# Sensor_Box_CAN_Switch.net
KiCad netlist of a schematic drawn in Altium Designer
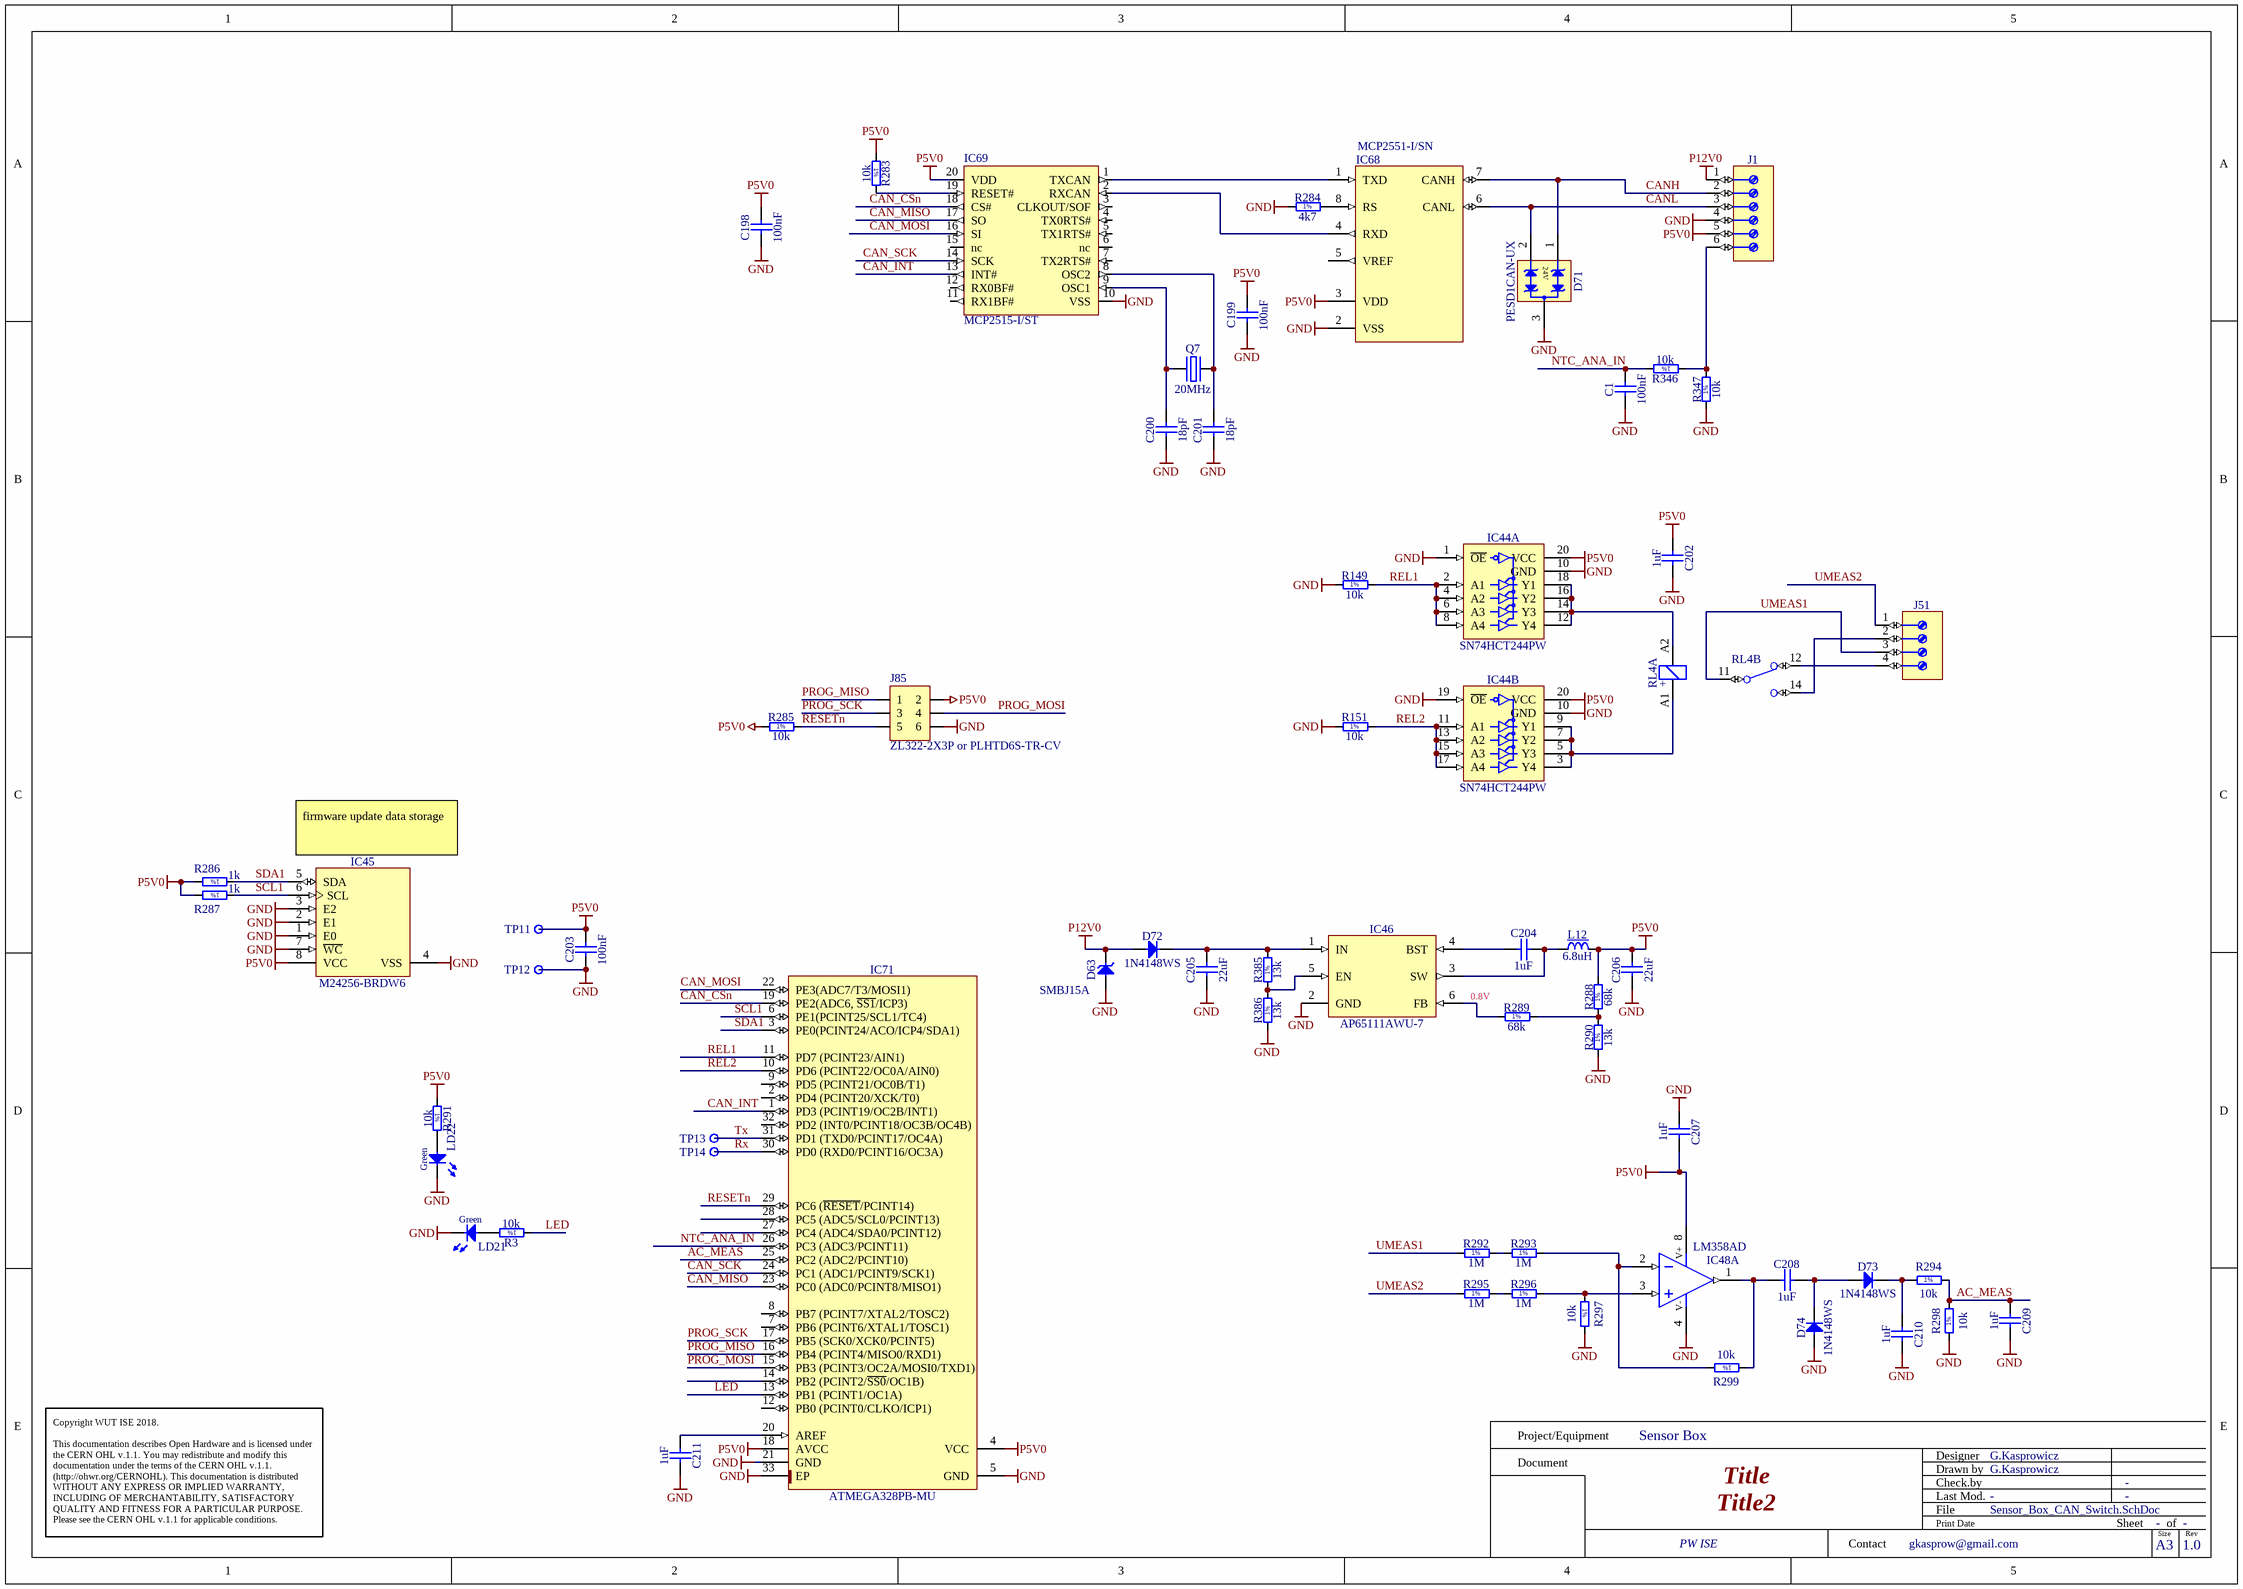
[diagram p0: Sensor_Box_CAN_Switch.SchDoc]

(export (version "E")
  (design (tool "Eeschema 10.0.6"))
  (components
    (comp (ref "C1")
      (value "100nF")
      (footprint "CAPC1005X55N")
      (description "Non-polarised capacitor")
      (fields
        (field (name "PART NUMBER") "CC0402_100NF_16V_10%_X5R")
        (field (name "VOLTAGE") "16V")
        (field (name "AUTHOR") "CERN DEM JLC")
      )
      (libsource (lib "Capacitors") (part "Capacitor - non polarized"))
    )
    (comp (ref "C198")
      (value "100nF")
      (footprint "CAPC1005X55N")
      (description "Non-polarised capacitor")
      (fields
        (field (name "PART NUMBER") "CC0402_100NF_16V_10%_X5R")
        (field (name "VOLTAGE") "16V")
        (field (name "AUTHOR") "CERN DEM JLC")
      )
      (libsource (lib "Capacitors") (part "Capacitor - non polarized"))
    )
    (comp (ref "C199")
      (value "100nF")
      (footprint "CAPC1005X55N")
      (description "Non-polarised capacitor")
      (fields
        (field (name "PART NUMBER") "CC0402_100NF_16V_10%_X5R")
        (field (name "VOLTAGE") "16V")
        (field (name "AUTHOR") "CERN DEM JLC")
      )
      (libsource (lib "Capacitors") (part "Capacitor - non polarized"))
    )
    (comp (ref "C200")
      (value "18pF")
      (footprint "CAPC1005X55N")
      (description "Non-polarised capacitor")
      (fields
        (field (name "PART NUMBER") "CC0402_18PF_50V_5%_C0G")
        (field (name "VOLTAGE") "50V")
        (field (name "AUTHOR") "CERN DEM JLC")
      )
      (libsource (lib "Capacitors") (part "Capacitor - non polarized"))
    )
    (comp (ref "C201")
      (value "18pF")
      (footprint "CAPC1005X55N")
      (description "Non-polarised capacitor")
      (fields
        (field (name "PART NUMBER") "CC0402_18PF_50V_5%_C0G")
        (field (name "VOLTAGE") "50V")
        (field (name "AUTHOR") "CERN DEM JLC")
      )
      (libsource (lib "Capacitors") (part "Capacitor - non polarized"))
    )
    (comp (ref "C202")
      (value "1uF")
      (footprint "CAPC1005X55N")
      (description "Non-polarised capacitor")
      (fields
        (field (name "PART NUMBER") "CC0402_1UF_16V_10%_X5R")
        (field (name "VOLTAGE") "16V")
        (field (name "AUTHOR") "CERN DEM JLC")
      )
      (libsource (lib "Capacitors") (part "Capacitor - non polarized"))
    )
    (comp (ref "C203")
      (value "100nF")
      (footprint "CAPC1005X55N")
      (description "Non-polarised capacitor")
      (fields
        (field (name "PART NUMBER") "CC0402_100NF_16V_10%_X5R")
        (field (name "VOLTAGE") "16V")
        (field (name "AUTHOR") "CERN DEM JLC")
      )
      (libsource (lib "Capacitors") (part "Capacitor - non polarized"))
    )
    (comp (ref "C204")
      (value "1uF")
      (footprint "CAPC1005X55N")
      (description "Non-polarised capacitor")
      (fields
        (field (name "PART NUMBER") "CC0402_1UF_16V_10%_X5R")
        (field (name "VOLTAGE") "16V")
        (field (name "AUTHOR") "CERN DEM JLC")
      )
      (libsource (lib "Capacitors") (part "Capacitor - non polarized"))
    )
    (comp (ref "C205")
      (value "22uF")
      (footprint "CAPC1709X100N")
      (description "Non-polarised capacitor")
      (fields
        (field (name "PART NUMBER") "CC0603_22UF_6.3V_20%_X5R")
        (field (name "VOLTAGE") "6.3V")
        (field (name "AUTHOR") "CERN DEM JLC")
      )
      (libsource (lib "Capacitors") (part "Capacitor - non polarized"))
    )
    (comp (ref "C206")
      (value "22uF")
      (footprint "CAPC1709X100N")
      (description "Non-polarised capacitor")
      (fields
        (field (name "PART NUMBER") "CC0603_22UF_6.3V_20%_X5R")
        (field (name "VOLTAGE") "6.3V")
        (field (name "AUTHOR") "CERN DEM JLC")
      )
      (libsource (lib "Capacitors") (part "Capacitor - non polarized"))
    )
    (comp (ref "C207")
      (value "1uF")
      (footprint "CAPC1005X55N")
      (description "Non-polarised capacitor")
      (fields
        (field (name "PART NUMBER") "CC0402_1UF_16V_10%_X5R")
        (field (name "VOLTAGE") "16V")
        (field (name "AUTHOR") "CERN DEM JLC")
      )
      (libsource (lib "Capacitors") (part "Capacitor - non polarized"))
    )
    (comp (ref "C208")
      (value "1uF")
      (footprint "CAPC1005X55N")
      (description "Non-polarised capacitor")
      (fields
        (field (name "PART NUMBER") "CC0402_1UF_16V_10%_X5R")
        (field (name "VOLTAGE") "16V")
        (field (name "AUTHOR") "CERN DEM JLC")
      )
      (libsource (lib "Capacitors") (part "Capacitor - non polarized"))
    )
    (comp (ref "C209")
      (value "1uF")
      (footprint "CAPC1005X55N")
      (description "Non-polarised capacitor")
      (fields
        (field (name "PART NUMBER") "CC0402_1UF_16V_10%_X5R")
        (field (name "VOLTAGE") "16V")
        (field (name "AUTHOR") "CERN DEM JLC")
      )
      (libsource (lib "Capacitors") (part "Capacitor - non polarized"))
    )
    (comp (ref "C210")
      (value "1uF")
      (footprint "CAPC1005X55N")
      (description "Non-polarised capacitor")
      (fields
        (field (name "PART NUMBER") "CC0402_1UF_16V_10%_X5R")
        (field (name "VOLTAGE") "16V")
        (field (name "AUTHOR") "CERN DEM JLC")
      )
      (libsource (lib "Capacitors") (part "Capacitor - non polarized"))
    )
    (comp (ref "C211")
      (value "1uF")
      (footprint "CAPC1005X55N")
      (description "Non-polarised capacitor")
      (fields
        (field (name "PART NUMBER") "CC0402_1UF_16V_10%_X5R")
        (field (name "VOLTAGE") "16V")
        (field (name "AUTHOR") "CERN DEM JLC")
      )
      (libsource (lib "Capacitors") (part "Capacitor - non polarized"))
    )
    (comp (ref "D63")
      (value "SMBJ15A")
      (footprint "DIOM5336X265N")
      (description "Zener Diode")
      (fields
        (field (name "VOLTAGE") "15V")
        (field (name "POWER") "600W")
        (field (name "AUTHOR") "CERN DEM JLC")
      )
      (libsource (lib "ICs And Semiconductors") (part "Diode Zener"))
    )
    (comp (ref "D71")
      (value "PESD1CAN-UX")
      (footprint "SOT95P237X112-3N")
      (description "TVS Diode for CAN")
      (fields
        (field (name "VOLTAGE") "24V")
        (field (name "POWER") "400W")
        (field (name "AUTHOR") "CERN DEM JLC")
      )
      (libsource (lib "LIBRARY_SCH") (part "D_TVS_PESD1CAN"))
    )
    (comp (ref "D72")
      (value "1N4148WS")
      (footprint "SODFL2512X100N")
      (description "Diode")
      (fields
        (field (name "VOLTAGE") "75V")
        (field (name "POWER") "150mA")
        (field (name "AUTHOR") "CERN DEM JLC")
      )
      (libsource (lib "ICs And Semiconductors") (part "Diode"))
    )
    (comp (ref "D73")
      (value "1N4148WS")
      (footprint "SODFL2512X100N")
      (description "Diode")
      (fields
        (field (name "VOLTAGE") "75V")
        (field (name "POWER") "150mA")
        (field (name "AUTHOR") "CERN DEM JLC")
      )
      (libsource (lib "ICs And Semiconductors") (part "Diode"))
    )
    (comp (ref "D74")
      (value "1N4148WS")
      (footprint "SODFL2512X100N")
      (description "Diode")
      (fields
        (field (name "VOLTAGE") "75V")
        (field (name "POWER") "150mA")
        (field (name "AUTHOR") "CERN DEM JLC")
      )
      (libsource (lib "ICs And Semiconductors") (part "Diode"))
    )
    (comp (ref "IC44")
      (value "SN74HCT244PW")
      (footprint "SOP65P640X120-20N")
      (description "Octal Buffer/Driver with 3-State Ouputs")
      (fields (field (name "MANUFACTURER") "TEXAS INSTRUMENTS") (field (name "AUTHOR") "CERN DEM JLC"))
      (libsource (lib "ICs And Semiconductors") (part "74244_a"))
    )
    (comp (ref "IC45")
      (value "M24256-BRDW6")
      (footprint "SOP65P640X120-8N")
      (description "256-Kbit Serial I²C Bus EEPROM")
      (fields
        (field (name "PART NUMBER") "M24256-BRDW6P")
        (field (name "MANUFACTURER") "ST MICROELECTRONICS")
        (field (name "AUTHOR") "CERN DEM MR")
      )
      (libsource (lib "LIBRARY_SCH") (part "MEM_M24256-BRDW6P"))
    )
    (comp (ref "IC46")
      (value "AP65111AWU-7")
      (footprint "SOT95P280X100-6N")
      (description "Light Load Improved 1.5A Synch DC/DC Buck Converter")
      (fields (field (name "MANUFACTURER") "DIODES INCORPORATED") (field (name "AUTHOR") "CERN DEM JLC"))
      (libsource (lib "ICs And Semiconductors") (part "AP65111A"))
    )
    (comp (ref "IC48")
      (value "LM358AD")
      (footprint "SOIC127P600X175-8N")
      (description "Dual Operational Amplifier")
      (fields (field (name "MANUFACTURER") "TEXAS INSTRUMENTS") (field (name "AUTHOR") "CERN DEM JLC"))
      (libsource (lib "ICs And Semiconductors") (part "Operational Amplifier x2 Type1"))
    )
    (comp (ref "IC68")
      (value "MCP2551-I/SN")
      (footprint "SOIC127P600X175-8N")
      (description "High-Speed CAN Transceiver, 8-Pin SOIC, Industrial Temperature")
      (fields (field (name "MANUFACTURER") "MICROCHIP TECHNOLOGY") (field (name "AUTHOR") "GK"))
      (libsource (lib "LIBRARY_SCH") (part "IFC_MCP2551"))
    )
    (comp (ref "IC69")
      (value "MCP2515-I/ST")
      (footprint "SOP65P640X110-20N")
      (description "CAN Controller With SPI nterface")
      (fields
        (field (name "MANUFACTURER") "Microchip")
        (field (name "MANUFACTURER PART NUMBER") "MCP2515T-I/ST")
      )
      (libsource (lib "LIBRARY_SCH") (part "IFC_MCP2515_TSSOP"))
    )
    (comp (ref "IC71")
      (value "ATMEGA328PB-MU")
      (footprint "QFN50P500X500X100-33N-S325")
      (description "8-bit AVR 20MHz Microcontroller With 32K Bytes In-System  Programmable  Flash")
      (fields (field (name "MANUFACTURER") "ATMEL") (field (name "AUTHOR") "GK"))
      (libsource (lib "LIBRARY_SCH") (part "UPC_ATMEGA328PB-MU"))
    )
    (comp (ref "J1")
      (value "~")
      (footprint "PHOENIX_1725698")
      (description "Terminal Block, 6 Positions, Screw Connection")
      (fields
        (field (name "PART NUMBER") "PHOENIX_1725698")
        (field (name "MANUFACTURER") "PHOENIX CONTACT")
        (field (name "AUTHOR") "CERN DEM JMW")
      )
      (libsource (lib "Connectors") (part "Terminal Block_6 Positions_Screw Connection"))
    )
    (comp (ref "J51")
      (value "~")
      (footprint "TYCO_282836-4")
      (description "Terminal Block, 4 Positions, Screw Connection")
      (fields
        (field (name "PART NUMBER") "TYCO_282836-4")
        (field (name "MANUFACTURER") "TYCO ELECTRONICS")
        (field (name "AUTHOR") "CERN DEM JLC")
      )
      (libsource (lib "Connectors") (part "Terminal Block_4 Positions_Screw Connection"))
    )
    (comp (ref "J85")
      (value "ZL322-2X3P or PLHTD6S-TR-CV")
      (footprint "ZL322-2X3P")
      (description "1.27 mm dual row goldpin (Maritex)")
      (libsource (lib "LIBRARY_SCH") (part "CON_2x3 1.27 SMT Male"))
    )
    (comp (ref "L12")
      (value "6.8uH")
      (footprint "IND_WALSIN_WLPN3030")
      (description "6,8uH; 900mA; 0,211Ω; 3x3x1,5mm")
      (fields
        (field (name "PART NUMBER") "IND_6.8UH_20%_WALSIN_WLPN303015M6R8PB")
        (field (name "POWER") "900mA")
        (field (name "AUTHOR") "GK")
      )
      (libsource (lib "LIBRARY_SCH") (part "IND_WLPN3030"))
    )
    (comp (ref "LD21")
      (value "Green")
      (footprint "LED_KINGBRIGHT_KPH-1608CGCK")
      (description "LED Green 1C 2A")
      (fields
        (field (name "PART NUMBER") "LED_KINGBRIGHT_KPH-1608CGCK")
        (field (name "MANUFACTURER") "KINGBRIGHT")
        (field (name "AUTHOR") "CERN DEM JLC")
      )
      (libsource (lib "ICs And Semiconductors") (part "LED Green 1C 2A"))
    )
    (comp (ref "LD22")
      (value "Green")
      (footprint "LED_KINGBRIGHT_KPH-1608CGCK")
      (description "LED Green 1C 2A")
      (fields
        (field (name "PART NUMBER") "LED_KINGBRIGHT_KPH-1608CGCK")
        (field (name "MANUFACTURER") "KINGBRIGHT")
        (field (name "AUTHOR") "CERN DEM JLC")
      )
      (libsource (lib "ICs And Semiconductors") (part "LED Green 1C 2A"))
    )
    (comp (ref "Q7")
      (value "20MHz")
      (footprint "XTAL1160X490X430")
      (description "Quartz Crystal 20MHz, 30ppm, 20pF")
      (fields
        (field (name "PART NUMBER") "SR PASSIVES 20M-49SMD-SR")
        (field (name "MANUFACTURER") "SR PASSIVES")
        (field (name "AUTHOR") "GK")
      )
      (libsource (lib "LIBRARY_SCH") (part "X_CRYSTAL_20M_HC49"))
    )
    (comp (ref "R3")
      (value "10k")
      (footprint "RESC1005X40N")
      (description "Resistor - 1%")
      (fields
        (field (name "PART NUMBER") "R0402_10K_1%_0.0625W_100PPM")
        (field (name "POWER") "0.0625W")
        (field (name "AUTHOR") "CERN DEM JLC")
      )
      (libsource (lib "Resistors") (part "Resistor - 1%"))
    )
    (comp (ref "R149")
      (value "10k")
      (footprint "RESC1005X40N")
      (description "Resistor - 1%")
      (fields
        (field (name "PART NUMBER") "R0402_10K_1%_0.0625W_100PPM")
        (field (name "POWER") "0.0625W")
        (field (name "AUTHOR") "CERN DEM JLC")
      )
      (libsource (lib "Resistors") (part "Resistor - 1%"))
    )
    (comp (ref "R151")
      (value "10k")
      (footprint "RESC1005X40N")
      (description "Resistor - 1%")
      (fields
        (field (name "PART NUMBER") "R0402_10K_1%_0.0625W_100PPM")
        (field (name "POWER") "0.0625W")
        (field (name "AUTHOR") "CERN DEM JLC")
      )
      (libsource (lib "Resistors") (part "Resistor - 1%"))
    )
    (comp (ref "R283")
      (value "10k")
      (footprint "RESC1005X40N")
      (description "Resistor - 1%")
      (fields
        (field (name "PART NUMBER") "R0402_10K_1%_0.0625W_100PPM")
        (field (name "POWER") "0.0625W")
        (field (name "AUTHOR") "CERN DEM JLC")
      )
      (libsource (lib "Resistors") (part "Resistor - 1%"))
    )
    (comp (ref "R284")
      (value "4k7")
      (footprint "RESC1005X40N")
      (description "Resistor - 1%")
      (fields
        (field (name "PART NUMBER") "R0402_4K7_1%_0.0625W_100PPM")
        (field (name "POWER") "0.0625W")
        (field (name "AUTHOR") "CERN DEM JLC")
      )
      (libsource (lib "Resistors") (part "Resistor - 1%"))
    )
    (comp (ref "R285")
      (value "10k")
      (footprint "RESC1005X40N")
      (description "Resistor - 1%")
      (fields
        (field (name "PART NUMBER") "R0402_10K_1%_0.0625W_100PPM")
        (field (name "POWER") "0.0625W")
        (field (name "AUTHOR") "CERN DEM JLC")
      )
      (libsource (lib "Resistors") (part "Resistor - 1%"))
    )
    (comp (ref "R286")
      (value "1k")
      (footprint "RESC1005X40N")
      (description "Resistor - 1%")
      (fields
        (field (name "PART NUMBER") "R0402_1K_1%_0.0625W_100PPM")
        (field (name "POWER") "0.0625W")
        (field (name "AUTHOR") "CERN DEM JLC")
      )
      (libsource (lib "Resistors") (part "Resistor - 1%"))
    )
    (comp (ref "R287")
      (value "1k")
      (footprint "RESC1005X40N")
      (description "Resistor - 1%")
      (fields
        (field (name "PART NUMBER") "R0402_1K_1%_0.0625W_100PPM")
        (field (name "POWER") "0.0625W")
        (field (name "AUTHOR") "CERN DEM JLC")
      )
      (libsource (lib "Resistors") (part "Resistor - 1%"))
    )
    (comp (ref "R288")
      (value "68k")
      (footprint "RESC1005X40N")
      (description "Resistor - 1%")
      (fields
        (field (name "PART NUMBER") "R0402_68K_1%_0.0625W_100PPM")
        (field (name "POWER") "0.0625W")
        (field (name "AUTHOR") "CERN DEM JLC")
      )
      (libsource (lib "Resistors") (part "Resistor - 1%"))
    )
    (comp (ref "R289")
      (value "68k")
      (footprint "RESC1005X40N")
      (description "Resistor - 1%")
      (fields
        (field (name "PART NUMBER") "R0402_68K_1%_0.0625W_100PPM")
        (field (name "POWER") "0.0625W")
        (field (name "AUTHOR") "CERN DEM JLC")
      )
      (libsource (lib "Resistors") (part "Resistor - 1%"))
    )
    (comp (ref "R290")
      (value "13k")
      (footprint "RESC1005X40N")
      (description "Resistor - 1%")
      (fields
        (field (name "PART NUMBER") "R0402_13K_1%_0.0625W_100PPM")
        (field (name "POWER") "0.0625W")
        (field (name "AUTHOR") "CERN DEM JLC")
      )
      (libsource (lib "Resistors") (part "Resistor - 1%"))
    )
    (comp (ref "R291")
      (value "10k")
      (footprint "RESC1005X40N")
      (description "Resistor - 1%")
      (fields
        (field (name "PART NUMBER") "R0402_10K_1%_0.0625W_100PPM")
        (field (name "POWER") "0.0625W")
        (field (name "AUTHOR") "CERN DEM JLC")
      )
      (libsource (lib "Resistors") (part "Resistor - 1%"))
    )
    (comp (ref "R292")
      (value "1M")
      (footprint "RESC3216X65N")
      (description "Resistor - 1%")
      (fields
        (field (name "PART NUMBER") "R1206_1M_1%_0.25W_100PPM")
        (field (name "POWER") "0.25W")
        (field (name "AUTHOR") "CERN DEM JLC")
      )
      (libsource (lib "Resistors") (part "Resistor - 1%"))
    )
    (comp (ref "R293")
      (value "1M")
      (footprint "RESC3216X65N")
      (description "Resistor - 1%")
      (fields
        (field (name "PART NUMBER") "R1206_1M_1%_0.25W_100PPM")
        (field (name "POWER") "0.25W")
        (field (name "AUTHOR") "CERN DEM JLC")
      )
      (libsource (lib "Resistors") (part "Resistor - 1%"))
    )
    (comp (ref "R294")
      (value "10k")
      (footprint "RESC1005X40N")
      (description "Resistor - 1%")
      (fields
        (field (name "PART NUMBER") "R0402_10K_1%_0.0625W_100PPM")
        (field (name "POWER") "0.0625W")
        (field (name "AUTHOR") "CERN DEM JLC")
      )
      (libsource (lib "Resistors") (part "Resistor - 1%"))
    )
    (comp (ref "R295")
      (value "1M")
      (footprint "RESC3216X65N")
      (description "Resistor - 1%")
      (fields
        (field (name "PART NUMBER") "R1206_1M_1%_0.25W_100PPM")
        (field (name "POWER") "0.25W")
        (field (name "AUTHOR") "CERN DEM JLC")
      )
      (libsource (lib "Resistors") (part "Resistor - 1%"))
    )
    (comp (ref "R296")
      (value "1M")
      (footprint "RESC3216X65N")
      (description "Resistor - 1%")
      (fields
        (field (name "PART NUMBER") "R1206_1M_1%_0.25W_100PPM")
        (field (name "POWER") "0.25W")
        (field (name "AUTHOR") "CERN DEM JLC")
      )
      (libsource (lib "Resistors") (part "Resistor - 1%"))
    )
    (comp (ref "R297")
      (value "10k")
      (footprint "RESC1005X40N")
      (description "Resistor - 1%")
      (fields
        (field (name "PART NUMBER") "R0402_10K_1%_0.0625W_100PPM")
        (field (name "POWER") "0.0625W")
        (field (name "AUTHOR") "CERN DEM JLC")
      )
      (libsource (lib "Resistors") (part "Resistor - 1%"))
    )
    (comp (ref "R298")
      (value "10k")
      (footprint "RESC1005X40N")
      (description "Resistor - 1%")
      (fields
        (field (name "PART NUMBER") "R0402_10K_1%_0.0625W_100PPM")
        (field (name "POWER") "0.0625W")
        (field (name "AUTHOR") "CERN DEM JLC")
      )
      (libsource (lib "Resistors") (part "Resistor - 1%"))
    )
    (comp (ref "R299")
      (value "10k")
      (footprint "RESC1005X40N")
      (description "Resistor - 1%")
      (fields
        (field (name "PART NUMBER") "R0402_10K_1%_0.0625W_100PPM")
        (field (name "POWER") "0.0625W")
        (field (name "AUTHOR") "CERN DEM JLC")
      )
      (libsource (lib "Resistors") (part "Resistor - 1%"))
    )
    (comp (ref "R346")
      (value "10k")
      (footprint "RESC1005X40N")
      (description "Resistor - 1%")
      (fields
        (field (name "PART NUMBER") "R0402_10K_1%_0.0625W_100PPM")
        (field (name "POWER") "0.0625W")
        (field (name "AUTHOR") "CERN DEM JLC")
      )
      (libsource (lib "Resistors") (part "Resistor - 1%"))
    )
    (comp (ref "R347")
      (value "10k")
      (footprint "RESC1005X40N")
      (description "Resistor - 1%")
      (fields
        (field (name "PART NUMBER") "R0402_10K_1%_0.0625W_100PPM")
        (field (name "POWER") "0.0625W")
        (field (name "AUTHOR") "CERN DEM JLC")
      )
      (libsource (lib "Resistors") (part "Resistor - 1%"))
    )
    (comp (ref "R385")
      (value "13k")
      (footprint "RESC1005X40N")
      (description "Resistor - 1%")
      (fields
        (field (name "PART NUMBER") "R0402_13K_1%_0.0625W_100PPM")
        (field (name "POWER") "0.0625W")
        (field (name "AUTHOR") "CERN DEM JLC")
      )
      (libsource (lib "Resistors") (part "Resistor - 1%"))
    )
    (comp (ref "R386")
      (value "13k")
      (footprint "RESC1005X40N")
      (description "Resistor - 1%")
      (fields
        (field (name "PART NUMBER") "R0402_13K_1%_0.0625W_100PPM")
        (field (name "POWER") "0.0625W")
        (field (name "AUTHOR") "CERN DEM JLC")
      )
      (libsource (lib "Resistors") (part "Resistor - 1%"))
    )
    (comp (ref "RL4")
      (value "REL_TYCO_PE01")
      (footprint "REL_TYCO_PE01")
      (description "1 form C (CO) General Purpose Low Power PCB Relay, PE Series")
      (fields
        (field (name "PART NUMBER") "REL_TYCO_PE014F05")
        (field (name "MANUFACTURER") "TYCO SCHRACK")
        (field (name "AUTHOR") "CERN DEM JLC")
      )
      (libsource (lib "") (part "REL_TYCO_PE01_1"))
    )
    (comp (ref "TP11")
      (value "Test Point")
      (footprint "TPS127")
      (fields (field (name "PART NUMBER") "SMD_PAD_1.27X1.27MM") (field (name "AUTHOR") "CERN DEM JLC"))
      (libsource (lib "Eletro-mechanical") (part "Test Point"))
    )
    (comp (ref "TP12")
      (value "Test Point")
      (footprint "TPS127")
      (fields (field (name "PART NUMBER") "SMD_PAD_1.27X1.27MM") (field (name "AUTHOR") "CERN DEM JLC"))
      (libsource (lib "Eletro-mechanical") (part "Test Point"))
    )
    (comp (ref "TP13")
      (value "Test Point")
      (footprint "TPS127")
      (fields (field (name "PART NUMBER") "SMD_PAD_1.27X1.27MM") (field (name "AUTHOR") "CERN DEM JLC"))
      (libsource (lib "Eletro-mechanical") (part "Test Point"))
    )
    (comp (ref "TP14")
      (value "Test Point")
      (footprint "TPS127")
      (fields (field (name "PART NUMBER") "SMD_PAD_1.27X1.27MM") (field (name "AUTHOR") "CERN DEM JLC"))
      (libsource (lib "Eletro-mechanical") (part "Test Point"))
    )
  )
  (nets
    (net (code "1") (name "/AC_MEAS") (class "Default")
      (node (ref "C209") (pin "1") (pinfunction "1_1") (pintype "passive"))
      (node (ref "IC71") (pin "25") (pinfunction "PC2_(ADC2/PCINT10)_25") (pintype "bidirectional"))
      (node (ref "R294") (pin "2") (pinfunction "2_2") (pintype "passive"))
      (node (ref "R298") (pin "2") (pinfunction "2_2") (pintype "passive"))
    )
    (net (code "2") (name "/CANH") (class "Default")
      (node (ref "D71") (pin "1") (pinfunction "I/O1_1") (pintype "passive"))
      (node (ref "IC68") (pin "7") (pinfunction "CANH_7") (pintype "bidirectional"))
      (node (ref "J1") (pin "2") (pinfunction "2_2") (pintype "bidirectional"))
    )
    (net (code "3") (name "/CANL") (class "Default")
      (node (ref "D71") (pin "2") (pinfunction "I/O2_2") (pintype "passive"))
      (node (ref "IC68") (pin "6") (pinfunction "CANL_6") (pintype "bidirectional"))
      (node (ref "J1") (pin "3") (pinfunction "3_3") (pintype "bidirectional"))
    )
    (net (code "4") (name "/CAN_CSn") (class "Default")
      (node (ref "IC69") (pin "18") (pinfunction "CS#_18") (pintype "output"))
      (node (ref "IC71") (pin "19") (pinfunction "PE2(ADC6,_~{SS1}/ICP3)_19") (pintype "bidirectional"))
    )
    (net (code "5") (name "/CAN_INT") (class "Default")
      (node (ref "IC69") (pin "13") (pinfunction "INT#_13") (pintype "output"))
      (node (ref "IC71") (pin "1") (pinfunction "PD3_(PCINT19/OC2B/INT1)_1") (pintype "bidirectional"))
    )
    (net (code "6") (name "/CAN_MISO") (class "Default")
      (node (ref "IC69") (pin "17") (pinfunction "SO_17") (pintype "output"))
      (node (ref "IC71") (pin "23") (pinfunction "PC0_(ADC0/PCINT8/MISO1)_23") (pintype "bidirectional"))
    )
    (net (code "7") (name "/CAN_MOSI") (class "Default")
      (node (ref "IC69") (pin "16") (pinfunction "SI_16") (pintype "input"))
      (node (ref "IC71") (pin "22") (pinfunction "PE3(ADC7/T3/MOSI1)_22") (pintype "bidirectional"))
    )
    (net (code "8") (name "/CAN_SCK") (class "Default")
      (node (ref "IC69") (pin "14") (pinfunction "SCK_14") (pintype "input"))
      (node (ref "IC71") (pin "24") (pinfunction "PC1_(ADC1/PCINT9/SCK1)_24") (pintype "bidirectional"))
    )
    (net (code "9") (name "/LED") (class "Default")
      (node (ref "IC71") (pin "13") (pinfunction "PB1_(PCINT1/OC1A)_13") (pintype "bidirectional"))
      (node (ref "R3") (pin "1") (pinfunction "1_1") (pintype "passive"))
    )
    (net (code "10") (name "/NTC_ANA_IN") (class "Default")
      (node (ref "C1") (pin "2") (pinfunction "2_2") (pintype "passive"))
      (node (ref "IC71") (pin "26") (pinfunction "PC3_(ADC3/PCINT11)_26") (pintype "bidirectional"))
      (node (ref "R346") (pin "2") (pinfunction "2_2") (pintype "passive"))
    )
    (net (code "11") (name "/PROG_MISO") (class "Default")
      (node (ref "IC71") (pin "16") (pinfunction "PB4_(PCINT4/MISO0/RXD1)_16") (pintype "bidirectional"))
      (node (ref "J85") (pin "1") (pinfunction "1_1") (pintype "passive"))
    )
    (net (code "12") (name "/PROG_MOSI") (class "Default")
      (node (ref "IC71") (pin "15") (pinfunction "PB3_(PCINT3/OC2A/MOSI0/TXD1)_15") (pintype "bidirectional"))
      (node (ref "J85") (pin "4") (pinfunction "4_4") (pintype "passive"))
    )
    (net (code "13") (name "/PROG_SCK") (class "Default")
      (node (ref "IC71") (pin "17") (pinfunction "PB5_(SCK0/XCK0/PCINT5)_17") (pintype "bidirectional"))
      (node (ref "J85") (pin "3") (pinfunction "3_3") (pintype "passive"))
    )
    (net (code "14") (name "/REL1") (class "Default")
      (node (ref "IC44") (pin "2") (pinfunction "A1_2") (pintype "input"))
      (node (ref "IC44") (pin "4") (pinfunction "A2_4") (pintype "input"))
      (node (ref "IC44") (pin "6") (pinfunction "A3_6") (pintype "input"))
      (node (ref "IC44") (pin "8") (pinfunction "A4_8") (pintype "input"))
      (node (ref "IC71") (pin "11") (pinfunction "PD7_(PCINT23/AIN1)_11") (pintype "bidirectional"))
      (node (ref "R149") (pin "2") (pinfunction "2_2") (pintype "passive"))
    )
    (net (code "15") (name "/REL2") (class "Default")
      (node (ref "IC44") (pin "11") (pinfunction "A1_11") (pintype "input"))
      (node (ref "IC44") (pin "13") (pinfunction "A2_13") (pintype "input"))
      (node (ref "IC44") (pin "15") (pinfunction "A3_15") (pintype "input"))
      (node (ref "IC44") (pin "17") (pinfunction "A4_17") (pintype "input"))
      (node (ref "IC71") (pin "10") (pinfunction "PD6_(PCINT22/OC0A/AIN0)_10") (pintype "bidirectional"))
      (node (ref "R151") (pin "2") (pinfunction "2_2") (pintype "passive"))
    )
    (net (code "16") (name "/RESETn") (class "Default")
      (node (ref "IC71") (pin "29") (pinfunction "PC6_(~{RESET}/PCINT14)_29") (pintype "bidirectional"))
      (node (ref "J85") (pin "5") (pinfunction "5_5") (pintype "passive"))
      (node (ref "R285") (pin "2") (pinfunction "2_2") (pintype "passive"))
    )
    (net (code "17") (name "/Rx") (class "Default")
      (node (ref "IC71") (pin "30") (pinfunction "PD0_(RXD0/PCINT16/OC3A)_30") (pintype "bidirectional"))
      (node (ref "TP14") (pin "1") (pinfunction "1_1") (pintype "bidirectional"))
    )
    (net (code "18") (name "/SCL1") (class "Default")
      (node (ref "IC45") (pin "6") (pinfunction "SCL_6") (pintype "input"))
      (node (ref "IC71") (pin "6") (pinfunction "PE1(PCINT25/SCL1/TC4)_6") (pintype "bidirectional"))
      (node (ref "R287") (pin "1") (pinfunction "1_1") (pintype "passive"))
    )
    (net (code "19") (name "/SDA1") (class "Default")
      (node (ref "IC45") (pin "5") (pinfunction "SDA_5") (pintype "bidirectional"))
      (node (ref "IC71") (pin "3") (pinfunction "PE0(PCINT24/ACO/ICP4/SDA1)_3") (pintype "bidirectional"))
      (node (ref "R286") (pin "1") (pinfunction "1_1") (pintype "passive"))
    )
    (net (code "20") (name "/Tx") (class "Default")
      (node (ref "IC71") (pin "31") (pinfunction "PD1_(TXD0/PCINT17/OC4A)_31") (pintype "bidirectional"))
      (node (ref "TP13") (pin "1") (pinfunction "1_1") (pintype "bidirectional"))
    )
    (net (code "21") (name "/UMEAS1") (class "Default")
      (node (ref "J51") (pin "3") (pinfunction "3_3") (pintype "bidirectional"))
      (node (ref "R292") (pin "1") (pinfunction "1_1") (pintype "passive"))
      (node (ref "RL4") (pin "11") (pinfunction "C_11") (pintype "bidirectional"))
    )
    (net (code "22") (name "/UMEAS2") (class "Default")
      (node (ref "J51") (pin "1") (pinfunction "1_1") (pintype "bidirectional"))
      (node (ref "R295") (pin "1") (pinfunction "1_1") (pintype "passive"))
    )
    (net (code "23") (name "GND") (class "Default")
      (node (ref "C1") (pin "1") (pinfunction "1_1") (pintype "passive"))
      (node (ref "C198") (pin "1") (pinfunction "1_1") (pintype "passive"))
      (node (ref "C199") (pin "1") (pinfunction "1_1") (pintype "passive"))
      (node (ref "C200") (pin "1") (pinfunction "1_1") (pintype "passive"))
      (node (ref "C201") (pin "1") (pinfunction "1_1") (pintype "passive"))
      (node (ref "C202") (pin "2") (pinfunction "2_2") (pintype "passive"))
      (node (ref "C203") (pin "1") (pinfunction "1_1") (pintype "passive"))
      (node (ref "C205") (pin "1") (pinfunction "1_1") (pintype "passive"))
      (node (ref "C206") (pin "1") (pinfunction "1_1") (pintype "passive"))
      (node (ref "C207") (pin "1") (pinfunction "1_1") (pintype "passive"))
      (node (ref "C209") (pin "2") (pinfunction "2_2") (pintype "passive"))
      (node (ref "C210") (pin "2") (pinfunction "2_2") (pintype "passive"))
      (node (ref "C211") (pin "2") (pinfunction "2_2") (pintype "passive"))
      (node (ref "D63") (pin "2") (pinfunction "A_2") (pintype "passive"))
      (node (ref "D71") (pin "3") (pinfunction "GND_3") (pintype "passive"))
      (node (ref "D74") (pin "2") (pinfunction "A_2") (pintype "passive"))
      (node (ref "IC44") (pin "1") (pinfunction "~{OE}_1") (pintype "input"))
      (node (ref "IC44") (pin "10") (pinfunction "GND_10") (pintype "power_in"))
      (node (ref "IC44") (pin "19") (pinfunction "~{OE}_19") (pintype "input"))
      (node (ref "IC45") (pin "1") (pinfunction "E0_1") (pintype "input"))
      (node (ref "IC45") (pin "2") (pinfunction "E1_2") (pintype "input"))
      (node (ref "IC45") (pin "3") (pinfunction "E2_3") (pintype "input"))
      (node (ref "IC45") (pin "4") (pinfunction "VSS_4") (pintype "power_in"))
      (node (ref "IC45") (pin "7") (pinfunction "~{WC}_7") (pintype "input"))
      (node (ref "IC46") (pin "2") (pinfunction "GND_2") (pintype "power_in"))
      (node (ref "IC48") (pin "4") (pinfunction "V-_4") (pintype "power_in"))
      (node (ref "IC68") (pin "2") (pinfunction "VSS_2") (pintype "power_in"))
      (node (ref "IC69") (pin "10") (pinfunction "VSS_10") (pintype "power_in"))
      (node (ref "IC71") (pin "21") (pinfunction "GND_21") (pintype "power_in"))
      (node (ref "IC71") (pin "33") (pinfunction "EP_33") (pintype "power_in"))
      (node (ref "IC71") (pin "5") (pinfunction "GND_5") (pintype "power_in"))
      (node (ref "J1") (pin "4") (pinfunction "4_4") (pintype "bidirectional"))
      (node (ref "J85") (pin "6") (pinfunction "6_6") (pintype "passive"))
      (node (ref "LD21") (pin "1") (pinfunction "C_1") (pintype "passive"))
      (node (ref "LD22") (pin "1") (pinfunction "C_1") (pintype "passive"))
      (node (ref "R149") (pin "1") (pinfunction "1_1") (pintype "passive"))
      (node (ref "R151") (pin "1") (pinfunction "1_1") (pintype "passive"))
      (node (ref "R284") (pin "1") (pinfunction "1_1") (pintype "passive"))
      (node (ref "R290") (pin "1") (pinfunction "1_1") (pintype "passive"))
      (node (ref "R297") (pin "2") (pinfunction "2_2") (pintype "passive"))
      (node (ref "R298") (pin "1") (pinfunction "1_1") (pintype "passive"))
      (node (ref "R347") (pin "1") (pinfunction "1_1") (pintype "passive"))
      (node (ref "R386") (pin "1") (pinfunction "1_1") (pintype "passive"))
      (node (ref "TP12") (pin "1") (pinfunction "1_1") (pintype "bidirectional"))
    )
    (net (code "24") (name "Net-(D72-C)") (class "Default")
      (node (ref "C205") (pin "2") (pinfunction "2_2") (pintype "passive"))
      (node (ref "D72") (pin "1") (pinfunction "C_1") (pintype "passive"))
      (node (ref "IC46") (pin "1") (pinfunction "IN_1") (pintype "input"))
      (node (ref "R385") (pin "2") (pinfunction "2_2") (pintype "passive"))
    )
    (net (code "25") (name "Net-(D73-A)") (class "Default")
      (node (ref "C208") (pin "2") (pinfunction "2_2") (pintype "passive"))
      (node (ref "D73") (pin "2") (pinfunction "A_2") (pintype "passive"))
      (node (ref "D74") (pin "1") (pinfunction "C_1") (pintype "passive"))
    )
    (net (code "26") (name "Net-(D73-C)") (class "Default")
      (node (ref "C210") (pin "1") (pinfunction "1_1") (pintype "passive"))
      (node (ref "D73") (pin "1") (pinfunction "C_1") (pintype "passive"))
      (node (ref "R294") (pin "1") (pinfunction "1_1") (pintype "passive"))
    )
    (net (code "27") (name "Net-(IC44A-Y1)") (class "Default")
      (node (ref "IC44") (pin "12") (pinfunction "Y4_12") (pintype "tri_state"))
      (node (ref "IC44") (pin "14") (pinfunction "Y3_14") (pintype "tri_state"))
      (node (ref "IC44") (pin "16") (pinfunction "Y2_16") (pintype "tri_state"))
      (node (ref "IC44") (pin "18") (pinfunction "Y1_18") (pintype "tri_state"))
      (node (ref "RL4") (pin "A2") (pinfunction "A2_A2") (pintype "passive"))
    )
    (net (code "28") (name "Net-(IC44B-Y1)") (class "Default")
      (node (ref "IC44") (pin "3") (pinfunction "Y4_3") (pintype "tri_state"))
      (node (ref "IC44") (pin "5") (pinfunction "Y3_5") (pintype "tri_state"))
      (node (ref "IC44") (pin "7") (pinfunction "Y2_7") (pintype "tri_state"))
      (node (ref "IC44") (pin "9") (pinfunction "Y1_9") (pintype "tri_state"))
      (node (ref "RL4") (pin "A1") (pinfunction "A1_A1") (pintype "passive"))
    )
    (net (code "29") (name "Net-(IC46-BST)") (class "Default")
      (node (ref "C204") (pin "1") (pinfunction "1_1") (pintype "passive"))
      (node (ref "IC46") (pin "4") (pinfunction "BST_4") (pintype "input"))
    )
    (net (code "30") (name "Net-(IC46-EN)") (class "Default")
      (node (ref "IC46") (pin "5") (pinfunction "EN_5") (pintype "input"))
      (node (ref "R385") (pin "1") (pinfunction "1_1") (pintype "passive"))
      (node (ref "R386") (pin "2") (pinfunction "2_2") (pintype "passive"))
    )
    (net (code "31") (name "Net-(IC46-FB)") (class "Default")
      (node (ref "IC46") (pin "6") (pinfunction "FB_6") (pintype "input"))
      (node (ref "R289") (pin "1") (pinfunction "1_1") (pintype "passive"))
    )
    (net (code "32") (name "Net-(IC46-SW)") (class "Default")
      (node (ref "C204") (pin "2") (pinfunction "2_2") (pintype "passive"))
      (node (ref "IC46") (pin "3") (pinfunction "SW_3") (pintype "output"))
      (node (ref "L12") (pin "1") (pinfunction "1_1") (pintype "passive"))
    )
    (net (code "33") (name "Net-(IC48A-IN+)") (class "Default")
      (node (ref "IC48") (pin "3") (pinfunction "IN+_3") (pintype "input"))
      (node (ref "R296") (pin "2") (pinfunction "2_2") (pintype "passive"))
      (node (ref "R297") (pin "1") (pinfunction "1_1") (pintype "passive"))
    )
    (net (code "34") (name "Net-(IC48A-IN-)") (class "Default")
      (node (ref "IC48") (pin "2") (pinfunction "IN-_2") (pintype "input"))
      (node (ref "R293") (pin "2") (pinfunction "2_2") (pintype "passive"))
      (node (ref "R299") (pin "2") (pinfunction "2_2") (pintype "passive"))
    )
    (net (code "35") (name "Net-(IC48A-OUT)") (class "Default")
      (node (ref "C208") (pin "1") (pinfunction "1_1") (pintype "passive"))
      (node (ref "IC48") (pin "1") (pinfunction "OUT_1") (pintype "output"))
      (node (ref "R299") (pin "1") (pinfunction "1_1") (pintype "passive"))
    )
    (net (code "36") (name "Net-(IC68-RS)") (class "Default")
      (node (ref "IC68") (pin "8") (pinfunction "RS_8") (pintype "input"))
      (node (ref "R284") (pin "2") (pinfunction "2_2") (pintype "passive"))
    )
    (net (code "37") (name "Net-(IC68-RXD)") (class "Default")
      (node (ref "IC68") (pin "4") (pinfunction "RXD_4") (pintype "output"))
      (node (ref "IC69") (pin "2") (pinfunction "RXCAN_2") (pintype "input"))
    )
    (net (code "38") (name "Net-(IC68-TXD)") (class "Default")
      (node (ref "IC68") (pin "1") (pinfunction "TXD_1") (pintype "input"))
      (node (ref "IC69") (pin "1") (pinfunction "TXCAN_1") (pintype "output"))
    )
    (net (code "39") (name "Net-(IC69-OSC1)") (class "Default")
      (node (ref "C200") (pin "2") (pinfunction "2_2") (pintype "passive"))
      (node (ref "IC69") (pin "9") (pinfunction "OSC1_9") (pintype "input"))
      (node (ref "Q7") (pin "1") (pinfunction "OSC1_1") (pintype "passive"))
    )
    (net (code "40") (name "Net-(IC69-OSC2)") (class "Default")
      (node (ref "C201") (pin "2") (pinfunction "2_2") (pintype "passive"))
      (node (ref "IC69") (pin "8") (pinfunction "OSC2_8") (pintype "output"))
      (node (ref "Q7") (pin "2") (pinfunction "OSC2_2") (pintype "passive"))
    )
    (net (code "41") (name "Net-(IC69-RESET#)") (class "Default")
      (node (ref "IC69") (pin "19") (pinfunction "RESET#_19") (pintype "input"))
      (node (ref "R283") (pin "2") (pinfunction "2_2") (pintype "passive"))
    )
    (net (code "42") (name "Net-(IC71-AREF)") (class "Default")
      (node (ref "C211") (pin "1") (pinfunction "1_1") (pintype "passive"))
      (node (ref "IC71") (pin "20") (pinfunction "AREF_20") (pintype "input"))
    )
    (net (code "43") (name "Net-(J1-Pad6)") (class "Default")
      (node (ref "J1") (pin "6") (pinfunction "6_6") (pintype "bidirectional"))
      (node (ref "R346") (pin "1") (pinfunction "1_1") (pintype "passive"))
      (node (ref "R347") (pin "2") (pinfunction "2_2") (pintype "passive"))
    )
    (net (code "44") (name "Net-(LD21-A)") (class "Default")
      (node (ref "LD21") (pin "2") (pinfunction "A_2") (pintype "passive"))
      (node (ref "R3") (pin "2") (pinfunction "2_2") (pintype "passive"))
    )
    (net (code "45") (name "Net-(LD22-A)") (class "Default")
      (node (ref "LD22") (pin "2") (pinfunction "A_2") (pintype "passive"))
      (node (ref "R291") (pin "2") (pinfunction "2_2") (pintype "passive"))
    )
    (net (code "46") (name "Net-(R288-Pad1)") (class "Default")
      (node (ref "R288") (pin "1") (pinfunction "1_1") (pintype "passive"))
      (node (ref "R289") (pin "2") (pinfunction "2_2") (pintype "passive"))
      (node (ref "R290") (pin "2") (pinfunction "2_2") (pintype "passive"))
    )
    (net (code "47") (name "Net-(R292-Pad2)") (class "Default")
      (node (ref "R292") (pin "2") (pinfunction "2_2") (pintype "passive"))
      (node (ref "R293") (pin "1") (pinfunction "1_1") (pintype "passive"))
    )
    (net (code "48") (name "Net-(R295-Pad2)") (class "Default")
      (node (ref "R295") (pin "2") (pinfunction "2_2") (pintype "passive"))
      (node (ref "R296") (pin "1") (pinfunction "1_1") (pintype "passive"))
    )
    (net (code "49") (name "Net-(RL4B-NC)") (class "Default")
      (node (ref "J51") (pin "4") (pinfunction "4_4") (pintype "bidirectional"))
      (node (ref "RL4") (pin "12") (pinfunction "NC_12") (pintype "bidirectional"))
    )
    (net (code "50") (name "Net-(RL4B-NO)") (class "Default")
      (node (ref "J51") (pin "2") (pinfunction "2_2") (pintype "bidirectional"))
      (node (ref "RL4") (pin "14") (pinfunction "NO_14") (pintype "bidirectional"))
    )
    (net (code "51") (name "P5V0") (class "Default")
      (node (ref "C198") (pin "2") (pinfunction "2_2") (pintype "passive"))
      (node (ref "C199") (pin "2") (pinfunction "2_2") (pintype "passive"))
      (node (ref "C202") (pin "1") (pinfunction "1_1") (pintype "passive"))
      (node (ref "C203") (pin "2") (pinfunction "2_2") (pintype "passive"))
      (node (ref "C206") (pin "2") (pinfunction "2_2") (pintype "passive"))
      (node (ref "C207") (pin "2") (pinfunction "2_2") (pintype "passive"))
      (node (ref "IC44") (pin "20") (pinfunction "VCC_20") (pintype "power_in"))
      (node (ref "IC45") (pin "8") (pinfunction "VCC_8") (pintype "power_in"))
      (node (ref "IC48") (pin "8") (pinfunction "V+_8") (pintype "power_in"))
      (node (ref "IC68") (pin "3") (pinfunction "VDD_3") (pintype "power_in"))
      (node (ref "IC69") (pin "20") (pinfunction "VDD_20") (pintype "power_in"))
      (node (ref "IC71") (pin "18") (pinfunction "AVCC_18") (pintype "power_in"))
      (node (ref "IC71") (pin "4") (pinfunction "VCC_4") (pintype "power_in"))
      (node (ref "J1") (pin "5") (pinfunction "5_5") (pintype "bidirectional"))
      (node (ref "J85") (pin "2") (pinfunction "2_2") (pintype "passive"))
      (node (ref "L12") (pin "2") (pinfunction "2_2") (pintype "passive"))
      (node (ref "R283") (pin "1") (pinfunction "1_1") (pintype "passive"))
      (node (ref "R285") (pin "1") (pinfunction "1_1") (pintype "passive"))
      (node (ref "R286") (pin "2") (pinfunction "2_2") (pintype "passive"))
      (node (ref "R287") (pin "2") (pinfunction "2_2") (pintype "passive"))
      (node (ref "R288") (pin "2") (pinfunction "2_2") (pintype "passive"))
      (node (ref "R291") (pin "1") (pinfunction "1_1") (pintype "passive"))
      (node (ref "TP11") (pin "1") (pinfunction "1_1") (pintype "bidirectional"))
    )
    (net (code "52") (name "P12V0") (class "Default")
      (node (ref "D63") (pin "1") (pinfunction "C_1") (pintype "passive"))
      (node (ref "D72") (pin "2") (pinfunction "A_2") (pintype "passive"))
      (node (ref "J1") (pin "1") (pinfunction "1_1") (pintype "bidirectional"))
    )
    (net (code "53") (name "unconnected-(IC68-VREF-Pad5)") (class "Default")
      (node (ref "IC68") (pin "5") (pinfunction "VREF_5") (pintype "output"))
    )
    (net (code "54") (name "unconnected-(IC69-CLKOUT{slash}SOF-Pad3)") (class "Default")
      (node (ref "IC69") (pin "3") (pinfunction "CLKOUT/SOF_3") (pintype "output"))
    )
    (net (code "55") (name "unconnected-(IC69-RX0BF#-Pad12)") (class "Default")
      (node (ref "IC69") (pin "12") (pinfunction "RX0BF#_12") (pintype "output"))
    )
    (net (code "56") (name "unconnected-(IC69-RX1BF#-Pad11)") (class "Default")
      (node (ref "IC69") (pin "11") (pinfunction "RX1BF#_11") (pintype "output"))
    )
    (net (code "57") (name "unconnected-(IC69-TX0RTS#-Pad4)") (class "Default")
      (node (ref "IC69") (pin "4") (pinfunction "TX0RTS#_4") (pintype "input"))
    )
    (net (code "58") (name "unconnected-(IC69-TX1RTS#-Pad5)") (class "Default")
      (node (ref "IC69") (pin "5") (pinfunction "TX1RTS#_5") (pintype "input"))
    )
    (net (code "59") (name "unconnected-(IC69-TX2RTS#-Pad7)") (class "Default")
      (node (ref "IC69") (pin "7") (pinfunction "TX2RTS#_7") (pintype "input"))
    )
    (net (code "60") (name "unconnected-(IC69-nc-Pad6)") (class "Default")
      (node (ref "IC69") (pin "6") (pinfunction "nc_6") (pintype "passive"))
    )
    (net (code "61") (name "unconnected-(IC69-nc-Pad15)") (class "Default")
      (node (ref "IC69") (pin "15") (pinfunction "nc_15") (pintype "passive"))
    )
    (net (code "62") (name "unconnected-(IC71-PB0_(PCINT0{slash}CLKO{slash}ICP1)-Pad12)") (class "Default")
      (node (ref "IC71") (pin "12") (pinfunction "PB0_(PCINT0/CLKO/ICP1)_12") (pintype "bidirectional"))
    )
    (net (code "63") (name "unconnected-(IC71-PB2_(PCINT2{slash}~{SS0}{slash}OC1B)-Pad14)") (class "Default")
      (node (ref "IC71") (pin "14") (pinfunction "PB2_(PCINT2/~{SS0}/OC1B)_14") (pintype "bidirectional"))
    )
    (net (code "64") (name "unconnected-(IC71-PB6_(PCINT6{slash}XTAL1{slash}TOSC1)-Pad7)") (class "Default")
      (node (ref "IC71") (pin "7") (pinfunction "PB6_(PCINT6/XTAL1/TOSC1)_7") (pintype "bidirectional"))
    )
    (net (code "65") (name "unconnected-(IC71-PB7_(PCINT7{slash}XTAL2{slash}TOSC2)-Pad8)") (class "Default")
      (node (ref "IC71") (pin "8") (pinfunction "PB7_(PCINT7/XTAL2/TOSC2)_8") (pintype "bidirectional"))
    )
    (net (code "66") (name "unconnected-(IC71-PC4_(ADC4{slash}SDA0{slash}PCINT12)-Pad27)") (class "Default")
      (node (ref "IC71") (pin "27") (pinfunction "PC4_(ADC4/SDA0/PCINT12)_27") (pintype "bidirectional"))
    )
    (net (code "67") (name "unconnected-(IC71-PC5_(ADC5{slash}SCL0{slash}PCINT13)-Pad28)") (class "Default")
      (node (ref "IC71") (pin "28") (pinfunction "PC5_(ADC5/SCL0/PCINT13)_28") (pintype "bidirectional"))
    )
    (net (code "68") (name "unconnected-(IC71-PD2_(INT0{slash}PCINT18{slash}OC3B{slash}OC4B)-Pad32)") (class "Default")
      (node (ref "IC71") (pin "32") (pinfunction "PD2_(INT0/PCINT18/OC3B/OC4B)_32") (pintype "bidirectional"))
    )
    (net (code "69") (name "unconnected-(IC71-PD4_(PCINT20{slash}XCK{slash}T0)-Pad2)") (class "Default")
      (node (ref "IC71") (pin "2") (pinfunction "PD4_(PCINT20/XCK/T0)_2") (pintype "bidirectional"))
    )
    (net (code "70") (name "unconnected-(IC71-PD5_(PCINT21{slash}OC0B{slash}T1)-Pad9)") (class "Default")
      (node (ref "IC71") (pin "9") (pinfunction "PD5_(PCINT21/OC0B/T1)_9") (pintype "bidirectional"))
    )
  )
)
